# indicator.net
KiCad netlist of a schematic drawn in EAGLE
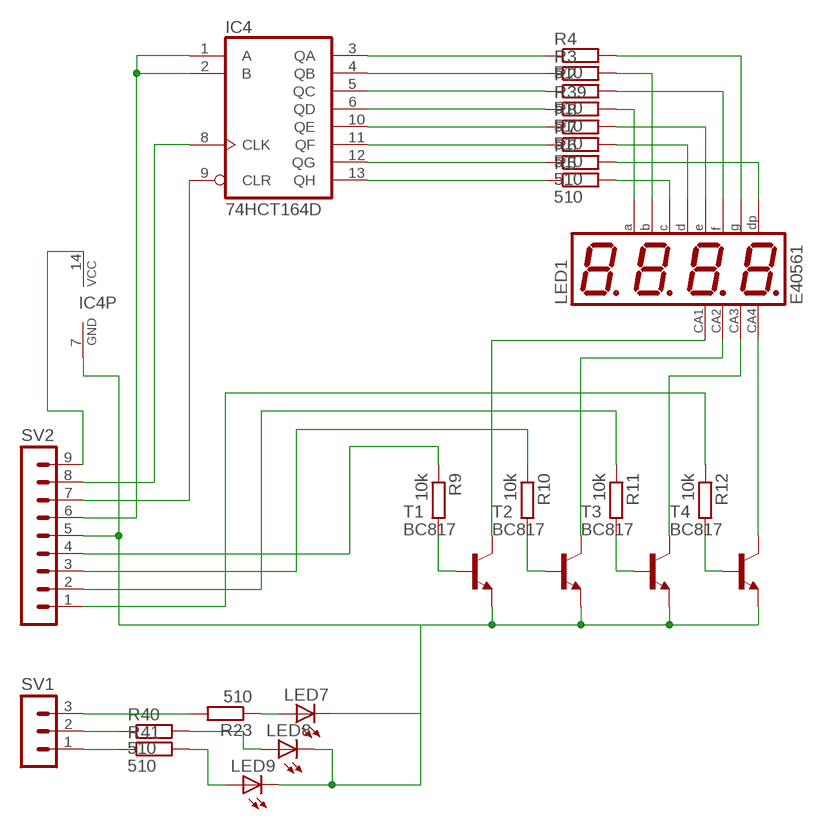
[diagram p0: schematic, sheet 1]

(export (version "E")
  (design (tool "Eeschema 10.0.6"))
  (components
    (comp (ref "IC4")
      (value "74HCT164D")
      (footprint "eagle-import:SO14")
      (libsource (lib "eagle-import") (part "74164DHCT"))
    )
    (comp (ref "LED1")
      (value "E40561")
      (footprint "eagle-import:BX56-12")
      (libsource (lib "eagle-import") (part "B?56-12WAAE"))
    )
    (comp (ref "LED7")
      (value "LED5MM")
      (footprint "eagle-import:LED5MM")
      (libsource (lib "eagle-import") (part "LED5MM"))
    )
    (comp (ref "LED8")
      (value "LED5MM")
      (footprint "eagle-import:LED5MM")
      (libsource (lib "eagle-import") (part "LED5MM"))
    )
    (comp (ref "LED9")
      (value "LED5MM")
      (footprint "eagle-import:LED5MM")
      (libsource (lib "eagle-import") (part "LED5MM"))
    )
    (comp (ref "R2")
      (value "510")
      (footprint "eagle-import:R0805")
      (libsource (lib "eagle-import") (part "R-EU_R0805"))
    )
    (comp (ref "R3")
      (value "R-EU_R0805")
      (footprint "eagle-import:R0805")
      (libsource (lib "eagle-import") (part "R-EU_R0805"))
    )
    (comp (ref "R4")
      (value "510")
      (footprint "eagle-import:R0805")
      (libsource (lib "eagle-import") (part "R-EU_R0805"))
    )
    (comp (ref "R5")
      (value "510")
      (footprint "eagle-import:R0805")
      (libsource (lib "eagle-import") (part "R-EU_R0805"))
    )
    (comp (ref "R6")
      (value "510")
      (footprint "eagle-import:R0805")
      (libsource (lib "eagle-import") (part "R-EU_R0805"))
    )
    (comp (ref "R7")
      (value "510")
      (footprint "eagle-import:R0805")
      (libsource (lib "eagle-import") (part "R-EU_R0805"))
    )
    (comp (ref "R8")
      (value "510")
      (footprint "eagle-import:R0805")
      (libsource (lib "eagle-import") (part "R-EU_R0805"))
    )
    (comp (ref "R9")
      (value "10k")
      (footprint "eagle-import:R0805")
      (libsource (lib "eagle-import") (part "R-EU_R0805"))
    )
    (comp (ref "R10")
      (value "10k")
      (footprint "eagle-import:R0805")
      (libsource (lib "eagle-import") (part "R-EU_R0805"))
    )
    (comp (ref "R11")
      (value "10k")
      (footprint "eagle-import:R0805")
      (libsource (lib "eagle-import") (part "R-EU_R0805"))
    )
    (comp (ref "R12")
      (value "10k")
      (footprint "eagle-import:R0805")
      (libsource (lib "eagle-import") (part "R-EU_R0805"))
    )
    (comp (ref "R23")
      (value "510")
      (footprint "eagle-import:R0805")
      (libsource (lib "eagle-import") (part "R-EU_R0805"))
    )
    (comp (ref "R39")
      (value "510")
      (footprint "eagle-import:R0805")
      (libsource (lib "eagle-import") (part "R-EU_R0805"))
    )
    (comp (ref "R40")
      (value "510")
      (footprint "eagle-import:R0805")
      (libsource (lib "eagle-import") (part "R-EU_R0805"))
    )
    (comp (ref "R41")
      (value "510")
      (footprint "eagle-import:R0805")
      (libsource (lib "eagle-import") (part "R-EU_R0805"))
    )
    (comp (ref "SV1")
      (value "MA03-1")
      (footprint "eagle-import:MA03-1")
      (libsource (lib "eagle-import") (part "MA03-1"))
    )
    (comp (ref "SV2")
      (value "MA09-1")
      (footprint "eagle-import:MA09-1")
      (libsource (lib "eagle-import") (part "MA09-1"))
    )
    (comp (ref "T1")
      (value "BC817")
      (footprint "eagle-import:SOT23-BEC")
      (libsource (lib "eagle-import") (part "-NPN-SOT23-BECBC817-16"))
    )
    (comp (ref "T2")
      (value "BC817")
      (footprint "eagle-import:SOT23-BEC")
      (libsource (lib "eagle-import") (part "-NPN-SOT23-BECBC817-16"))
    )
    (comp (ref "T3")
      (value "BC817")
      (footprint "eagle-import:SOT23-BEC")
      (libsource (lib "eagle-import") (part "-NPN-SOT23-BECBC817-16"))
    )
    (comp (ref "T4")
      (value "BC817")
      (footprint "eagle-import:SOT23-BEC")
      (libsource (lib "eagle-import") (part "-NPN-SOT23-BECBC817-16"))
    )
  )
  (nets
    (net (code "1") (name "Net-(IC4A-A)") (class "Default")
      (node (ref "IC4") (pin "1") (pinfunction "A_1") (pintype "input"))
      (node (ref "IC4") (pin "2") (pinfunction "B_2") (pintype "input"))
      (node (ref "SV2") (pin "6") (pinfunction "6_6") (pintype "passive"))
    )
    (net (code "2") (name "Net-(IC4A-CLK)") (class "Default")
      (node (ref "IC4") (pin "8") (pinfunction "CLK_8") (pintype "input"))
      (node (ref "SV2") (pin "8") (pinfunction "8_8") (pintype "passive"))
    )
    (net (code "3") (name "Net-(IC4A-CLR)") (class "Default")
      (node (ref "IC4") (pin "9") (pinfunction "CLR_9") (pintype "input"))
      (node (ref "SV2") (pin "7") (pinfunction "7_7") (pintype "passive"))
    )
    (net (code "4") (name "Net-(IC4A-QA)") (class "Default")
      (node (ref "IC4") (pin "3") (pinfunction "QA_3") (pintype "output"))
      (node (ref "R4") (pin "1") (pinfunction "1_1") (pintype "passive"))
    )
    (net (code "5") (name "Net-(IC4A-QB)") (class "Default")
      (node (ref "IC4") (pin "4") (pinfunction "QB_4") (pintype "output"))
      (node (ref "R3") (pin "1") (pinfunction "1_1") (pintype "passive"))
    )
    (net (code "6") (name "Net-(IC4A-QC)") (class "Default")
      (node (ref "IC4") (pin "5") (pinfunction "QC_5") (pintype "output"))
      (node (ref "R2") (pin "1") (pinfunction "1_1") (pintype "passive"))
    )
    (net (code "7") (name "Net-(IC4A-QD)") (class "Default")
      (node (ref "IC4") (pin "6") (pinfunction "QD_6") (pintype "output"))
      (node (ref "R39") (pin "1") (pinfunction "1_1") (pintype "passive"))
    )
    (net (code "8") (name "Net-(IC4A-QE)") (class "Default")
      (node (ref "IC4") (pin "10") (pinfunction "QE_10") (pintype "output"))
      (node (ref "R8") (pin "1") (pinfunction "1_1") (pintype "passive"))
    )
    (net (code "9") (name "Net-(IC4A-QF)") (class "Default")
      (node (ref "IC4") (pin "11") (pinfunction "QF_11") (pintype "output"))
      (node (ref "R7") (pin "1") (pinfunction "1_1") (pintype "passive"))
    )
    (net (code "10") (name "Net-(IC4A-QG)") (class "Default")
      (node (ref "IC4") (pin "12") (pinfunction "QG_12") (pintype "output"))
      (node (ref "R6") (pin "1") (pinfunction "1_1") (pintype "passive"))
    )
    (net (code "11") (name "Net-(IC4A-QH)") (class "Default")
      (node (ref "IC4") (pin "13") (pinfunction "QH_13") (pintype "output"))
      (node (ref "R5") (pin "1") (pinfunction "1_1") (pintype "passive"))
    )
    (net (code "12") (name "Net-(IC4B-GND)") (class "Default")
      (node (ref "IC4") (pin "7") (pinfunction "GND_7") (pintype "power_in"))
      (node (ref "LED7") (pin "K") (pinfunction "C_K") (pintype "passive"))
      (node (ref "LED8") (pin "K") (pinfunction "C_K") (pintype "passive"))
      (node (ref "LED9") (pin "K") (pinfunction "C_K") (pintype "passive"))
      (node (ref "SV2") (pin "5") (pinfunction "5_5") (pintype "passive"))
      (node (ref "T1") (pin "E") (pinfunction "E_E") (pintype "passive"))
      (node (ref "T2") (pin "E") (pinfunction "E_E") (pintype "passive"))
      (node (ref "T3") (pin "E") (pinfunction "E_E") (pintype "passive"))
      (node (ref "T4") (pin "E") (pinfunction "E_E") (pintype "passive"))
    )
    (net (code "13") (name "Net-(IC4B-VCC)") (class "Default")
      (node (ref "IC4") (pin "14") (pinfunction "VCC_14") (pintype "power_in"))
      (node (ref "SV2") (pin "9") (pinfunction "9_9") (pintype "passive"))
    )
    (net (code "14") (name "Net-(LED1-A)") (class "Default")
      (node (ref "LED1") (pin "11") (pinfunction "A_11") (pintype "passive"))
      (node (ref "R39") (pin "2") (pinfunction "2_2") (pintype "passive"))
    )
    (net (code "15") (name "Net-(LED1-B)") (class "Default")
      (node (ref "LED1") (pin "7") (pinfunction "B_7") (pintype "passive"))
      (node (ref "R3") (pin "2") (pinfunction "2_2") (pintype "passive"))
    )
    (net (code "16") (name "Net-(LED1-C)") (class "Default")
      (node (ref "LED1") (pin "4") (pinfunction "C_4") (pintype "passive"))
      (node (ref "R5") (pin "2") (pinfunction "2_2") (pintype "passive"))
    )
    (net (code "17") (name "Net-(LED1-CA-Pad6)") (class "Default")
      (node (ref "LED1") (pin "6") (pinfunction "CA_6") (pintype "passive"))
      (node (ref "T4") (pin "C") (pinfunction "C_C") (pintype "passive"))
    )
    (net (code "18") (name "Net-(LED1-CA-Pad8)") (class "Default")
      (node (ref "LED1") (pin "8") (pinfunction "CA_8") (pintype "passive"))
      (node (ref "T3") (pin "C") (pinfunction "C_C") (pintype "passive"))
    )
    (net (code "19") (name "Net-(LED1-CA-Pad9)") (class "Default")
      (node (ref "LED1") (pin "9") (pinfunction "CA_9") (pintype "passive"))
      (node (ref "T2") (pin "C") (pinfunction "C_C") (pintype "passive"))
    )
    (net (code "20") (name "Net-(LED1-CA-Pad12)") (class "Default")
      (node (ref "LED1") (pin "12") (pinfunction "CA_12") (pintype "passive"))
      (node (ref "T1") (pin "C") (pinfunction "C_C") (pintype "passive"))
    )
    (net (code "21") (name "Net-(LED1-D)") (class "Default")
      (node (ref "LED1") (pin "2") (pinfunction "D_2") (pintype "passive"))
      (node (ref "R7") (pin "2") (pinfunction "2_2") (pintype "passive"))
    )
    (net (code "22") (name "Net-(LED1-DP)") (class "Default")
      (node (ref "LED1") (pin "3") (pinfunction "DP_3") (pintype "passive"))
      (node (ref "R6") (pin "2") (pinfunction "2_2") (pintype "passive"))
    )
    (net (code "23") (name "Net-(LED1-E)") (class "Default")
      (node (ref "LED1") (pin "1") (pinfunction "E_1") (pintype "passive"))
      (node (ref "R8") (pin "2") (pinfunction "2_2") (pintype "passive"))
    )
    (net (code "24") (name "Net-(LED1-F)") (class "Default")
      (node (ref "LED1") (pin "10") (pinfunction "F_10") (pintype "passive"))
      (node (ref "R2") (pin "2") (pinfunction "2_2") (pintype "passive"))
    )
    (net (code "25") (name "Net-(LED1-G)") (class "Default")
      (node (ref "LED1") (pin "5") (pinfunction "G_5") (pintype "passive"))
      (node (ref "R4") (pin "2") (pinfunction "2_2") (pintype "passive"))
    )
    (net (code "26") (name "Net-(LED7-PadA)") (class "Default")
      (node (ref "LED7") (pin "A") (pinfunction "A_A") (pintype "passive"))
      (node (ref "R23") (pin "1") (pinfunction "1_1") (pintype "passive"))
    )
    (net (code "27") (name "Net-(LED8-PadA)") (class "Default")
      (node (ref "LED8") (pin "A") (pinfunction "A_A") (pintype "passive"))
      (node (ref "R40") (pin "2") (pinfunction "2_2") (pintype "passive"))
    )
    (net (code "28") (name "Net-(LED9-PadA)") (class "Default")
      (node (ref "LED9") (pin "A") (pinfunction "A_A") (pintype "passive"))
      (node (ref "R41") (pin "2") (pinfunction "2_2") (pintype "passive"))
    )
    (net (code "29") (name "Net-(R9-Pad1)") (class "Default")
      (node (ref "R9") (pin "1") (pinfunction "1_1") (pintype "passive"))
      (node (ref "SV2") (pin "4") (pinfunction "4_4") (pintype "passive"))
    )
    (net (code "30") (name "Net-(R9-Pad2)") (class "Default")
      (node (ref "R9") (pin "2") (pinfunction "2_2") (pintype "passive"))
      (node (ref "T1") (pin "B") (pinfunction "B_B") (pintype "passive"))
    )
    (net (code "31") (name "Net-(R10-Pad1)") (class "Default")
      (node (ref "R10") (pin "1") (pinfunction "1_1") (pintype "passive"))
      (node (ref "SV2") (pin "3") (pinfunction "3_3") (pintype "passive"))
    )
    (net (code "32") (name "Net-(R10-Pad2)") (class "Default")
      (node (ref "R10") (pin "2") (pinfunction "2_2") (pintype "passive"))
      (node (ref "T2") (pin "B") (pinfunction "B_B") (pintype "passive"))
    )
    (net (code "33") (name "Net-(R11-Pad1)") (class "Default")
      (node (ref "R11") (pin "1") (pinfunction "1_1") (pintype "passive"))
      (node (ref "SV2") (pin "2") (pinfunction "2_2") (pintype "passive"))
    )
    (net (code "34") (name "Net-(R11-Pad2)") (class "Default")
      (node (ref "R11") (pin "2") (pinfunction "2_2") (pintype "passive"))
      (node (ref "T3") (pin "B") (pinfunction "B_B") (pintype "passive"))
    )
    (net (code "35") (name "Net-(R12-Pad1)") (class "Default")
      (node (ref "R12") (pin "1") (pinfunction "1_1") (pintype "passive"))
      (node (ref "SV2") (pin "1") (pinfunction "1_1") (pintype "passive"))
    )
    (net (code "36") (name "Net-(R12-Pad2)") (class "Default")
      (node (ref "R12") (pin "2") (pinfunction "2_2") (pintype "passive"))
      (node (ref "T4") (pin "B") (pinfunction "B_B") (pintype "passive"))
    )
    (net (code "37") (name "Net-(R23-Pad2)") (class "Default")
      (node (ref "R23") (pin "2") (pinfunction "2_2") (pintype "passive"))
      (node (ref "SV1") (pin "3") (pinfunction "3_3") (pintype "passive"))
    )
    (net (code "38") (name "Net-(R40-Pad1)") (class "Default")
      (node (ref "R40") (pin "1") (pinfunction "1_1") (pintype "passive"))
      (node (ref "SV1") (pin "2") (pinfunction "2_2") (pintype "passive"))
    )
    (net (code "39") (name "Net-(R41-Pad1)") (class "Default")
      (node (ref "R41") (pin "1") (pinfunction "1_1") (pintype "passive"))
      (node (ref "SV1") (pin "1") (pinfunction "1_1") (pintype "passive"))
    )
  )
)
